# nodemcu_breakout.net
KiCad netlist of a schematic drawn in EAGLE
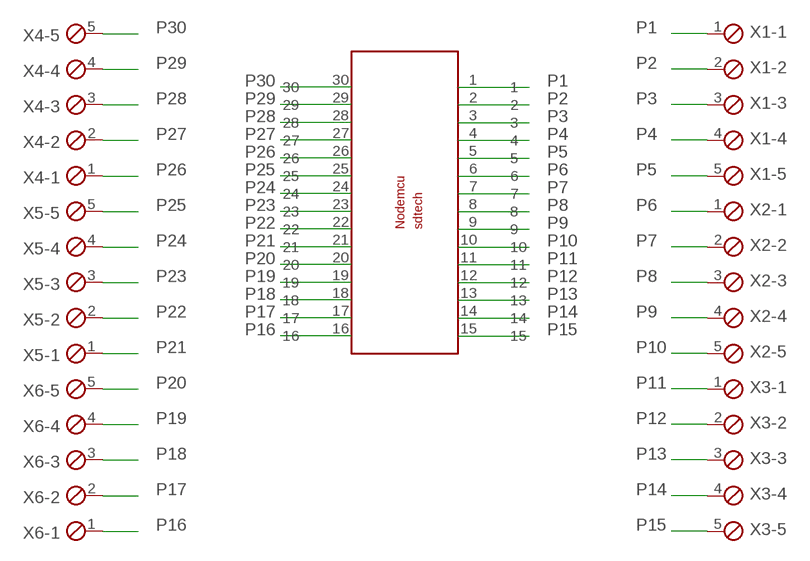
[diagram p0: schematic, sheet 1]

(export (version "E")
  (design (tool "Eeschema 10.0.6"))
  (components
    (comp (ref "U$1")
      (value "NODEMCUESP8266")
      (footprint "eagle-import:NODEMCUESP8266")
      (libsource (lib "eagle-import") (part "NODEMCUESP8266"))
    )
    (comp (ref "X1")
      (value "MPT5")
      (footprint "eagle-import:5POL254")
      (libsource (lib "eagle-import") (part "MPT5"))
    )
    (comp (ref "X2")
      (value "MPT5")
      (footprint "eagle-import:5POL254")
      (libsource (lib "eagle-import") (part "MPT5"))
    )
    (comp (ref "X3")
      (value "MPT5")
      (footprint "eagle-import:5POL254")
      (libsource (lib "eagle-import") (part "MPT5"))
    )
    (comp (ref "X4")
      (value "MPT5")
      (footprint "eagle-import:5POL254")
      (libsource (lib "eagle-import") (part "MPT5"))
    )
    (comp (ref "X5")
      (value "MPT5")
      (footprint "eagle-import:5POL254")
      (libsource (lib "eagle-import") (part "MPT5"))
    )
    (comp (ref "X6")
      (value "MPT5")
      (footprint "eagle-import:5POL254")
      (libsource (lib "eagle-import") (part "MPT5"))
    )
  )
  (nets
    (net (code "1") (name "/P1") (class "Default")
      (node (ref "U$1") (pin "1") (pinfunction "1_1") (pintype "bidirectional"))
      (node (ref "X1") (pin "1") (pinfunction "1_1") (pintype "passive"))
    )
    (net (code "2") (name "/P2") (class "Default")
      (node (ref "U$1") (pin "2") (pinfunction "2_2") (pintype "bidirectional"))
      (node (ref "X1") (pin "2") (pinfunction "1_2") (pintype "passive"))
    )
    (net (code "3") (name "/P3") (class "Default")
      (node (ref "U$1") (pin "3") (pinfunction "3_3") (pintype "bidirectional"))
      (node (ref "X1") (pin "3") (pinfunction "1_3") (pintype "passive"))
    )
    (net (code "4") (name "/P4") (class "Default")
      (node (ref "U$1") (pin "4") (pinfunction "4_4") (pintype "bidirectional"))
      (node (ref "X1") (pin "4") (pinfunction "1_4") (pintype "passive"))
    )
    (net (code "5") (name "/P5") (class "Default")
      (node (ref "U$1") (pin "5") (pinfunction "5_5") (pintype "bidirectional"))
      (node (ref "X1") (pin "5") (pinfunction "1_5") (pintype "passive"))
    )
    (net (code "6") (name "/P6") (class "Default")
      (node (ref "U$1") (pin "6") (pinfunction "6_6") (pintype "bidirectional"))
      (node (ref "X2") (pin "1") (pinfunction "1_1") (pintype "passive"))
    )
    (net (code "7") (name "/P7") (class "Default")
      (node (ref "U$1") (pin "7") (pinfunction "7_7") (pintype "bidirectional"))
      (node (ref "X2") (pin "2") (pinfunction "1_2") (pintype "passive"))
    )
    (net (code "8") (name "/P8") (class "Default")
      (node (ref "U$1") (pin "8") (pinfunction "8_8") (pintype "bidirectional"))
      (node (ref "X2") (pin "3") (pinfunction "1_3") (pintype "passive"))
    )
    (net (code "9") (name "/P9") (class "Default")
      (node (ref "U$1") (pin "9") (pinfunction "9_9") (pintype "bidirectional"))
      (node (ref "X2") (pin "4") (pinfunction "1_4") (pintype "passive"))
    )
    (net (code "10") (name "/P10") (class "Default")
      (node (ref "U$1") (pin "10") (pinfunction "10_10") (pintype "bidirectional"))
      (node (ref "X2") (pin "5") (pinfunction "1_5") (pintype "passive"))
    )
    (net (code "11") (name "/P11") (class "Default")
      (node (ref "U$1") (pin "11") (pinfunction "11_11") (pintype "bidirectional"))
      (node (ref "X3") (pin "1") (pinfunction "1_1") (pintype "passive"))
    )
    (net (code "12") (name "/P12") (class "Default")
      (node (ref "U$1") (pin "12") (pinfunction "12_12") (pintype "bidirectional"))
      (node (ref "X3") (pin "2") (pinfunction "1_2") (pintype "passive"))
    )
    (net (code "13") (name "/P13") (class "Default")
      (node (ref "U$1") (pin "13") (pinfunction "13_13") (pintype "bidirectional"))
      (node (ref "X3") (pin "3") (pinfunction "1_3") (pintype "passive"))
    )
    (net (code "14") (name "/P14") (class "Default")
      (node (ref "U$1") (pin "14") (pinfunction "14_14") (pintype "bidirectional"))
      (node (ref "X3") (pin "4") (pinfunction "1_4") (pintype "passive"))
    )
    (net (code "15") (name "/P15") (class "Default")
      (node (ref "U$1") (pin "15") (pinfunction "15_15") (pintype "bidirectional"))
      (node (ref "X3") (pin "5") (pinfunction "1_5") (pintype "passive"))
    )
    (net (code "16") (name "/P16") (class "Default")
      (node (ref "U$1") (pin "16") (pinfunction "16_16") (pintype "bidirectional"))
      (node (ref "X6") (pin "1") (pinfunction "1_1") (pintype "passive"))
    )
    (net (code "17") (name "/P17") (class "Default")
      (node (ref "U$1") (pin "17") (pinfunction "17_17") (pintype "bidirectional"))
      (node (ref "X6") (pin "2") (pinfunction "1_2") (pintype "passive"))
    )
    (net (code "18") (name "/P18") (class "Default")
      (node (ref "U$1") (pin "18") (pinfunction "18_18") (pintype "bidirectional"))
      (node (ref "X6") (pin "3") (pinfunction "1_3") (pintype "passive"))
    )
    (net (code "19") (name "/P19") (class "Default")
      (node (ref "U$1") (pin "19") (pinfunction "19_19") (pintype "bidirectional"))
      (node (ref "X6") (pin "4") (pinfunction "1_4") (pintype "passive"))
    )
    (net (code "20") (name "/P20") (class "Default")
      (node (ref "U$1") (pin "20") (pinfunction "20_20") (pintype "bidirectional"))
      (node (ref "X6") (pin "5") (pinfunction "1_5") (pintype "passive"))
    )
    (net (code "21") (name "/P21") (class "Default")
      (node (ref "U$1") (pin "21") (pinfunction "21_21") (pintype "bidirectional"))
      (node (ref "X5") (pin "1") (pinfunction "1_1") (pintype "passive"))
    )
    (net (code "22") (name "/P22") (class "Default")
      (node (ref "U$1") (pin "22") (pinfunction "22_22") (pintype "bidirectional"))
      (node (ref "X5") (pin "2") (pinfunction "1_2") (pintype "passive"))
    )
    (net (code "23") (name "/P23") (class "Default")
      (node (ref "U$1") (pin "23") (pinfunction "23_23") (pintype "bidirectional"))
      (node (ref "X5") (pin "3") (pinfunction "1_3") (pintype "passive"))
    )
    (net (code "24") (name "/P24") (class "Default")
      (node (ref "U$1") (pin "24") (pinfunction "24_24") (pintype "bidirectional"))
      (node (ref "X5") (pin "4") (pinfunction "1_4") (pintype "passive"))
    )
    (net (code "25") (name "/P25") (class "Default")
      (node (ref "U$1") (pin "25") (pinfunction "25_25") (pintype "bidirectional"))
      (node (ref "X5") (pin "5") (pinfunction "1_5") (pintype "passive"))
    )
    (net (code "26") (name "/P26") (class "Default")
      (node (ref "U$1") (pin "26") (pinfunction "26_26") (pintype "bidirectional"))
      (node (ref "X4") (pin "1") (pinfunction "1_1") (pintype "passive"))
    )
    (net (code "27") (name "/P27") (class "Default")
      (node (ref "U$1") (pin "27") (pinfunction "27_27") (pintype "bidirectional"))
      (node (ref "X4") (pin "2") (pinfunction "1_2") (pintype "passive"))
    )
    (net (code "28") (name "/P28") (class "Default")
      (node (ref "U$1") (pin "28") (pinfunction "28_28") (pintype "bidirectional"))
      (node (ref "X4") (pin "3") (pinfunction "1_3") (pintype "passive"))
    )
    (net (code "29") (name "/P29") (class "Default")
      (node (ref "U$1") (pin "29") (pinfunction "29_29") (pintype "bidirectional"))
      (node (ref "X4") (pin "4") (pinfunction "1_4") (pintype "passive"))
    )
    (net (code "30") (name "/P30") (class "Default")
      (node (ref "U$1") (pin "30") (pinfunction "30_30") (pintype "bidirectional"))
      (node (ref "X4") (pin "5") (pinfunction "1_5") (pintype "passive"))
    )
  )
)
